# OpenAT_Switch_Latch.net
KiCad netlist of a schematic drawn in EAGLE
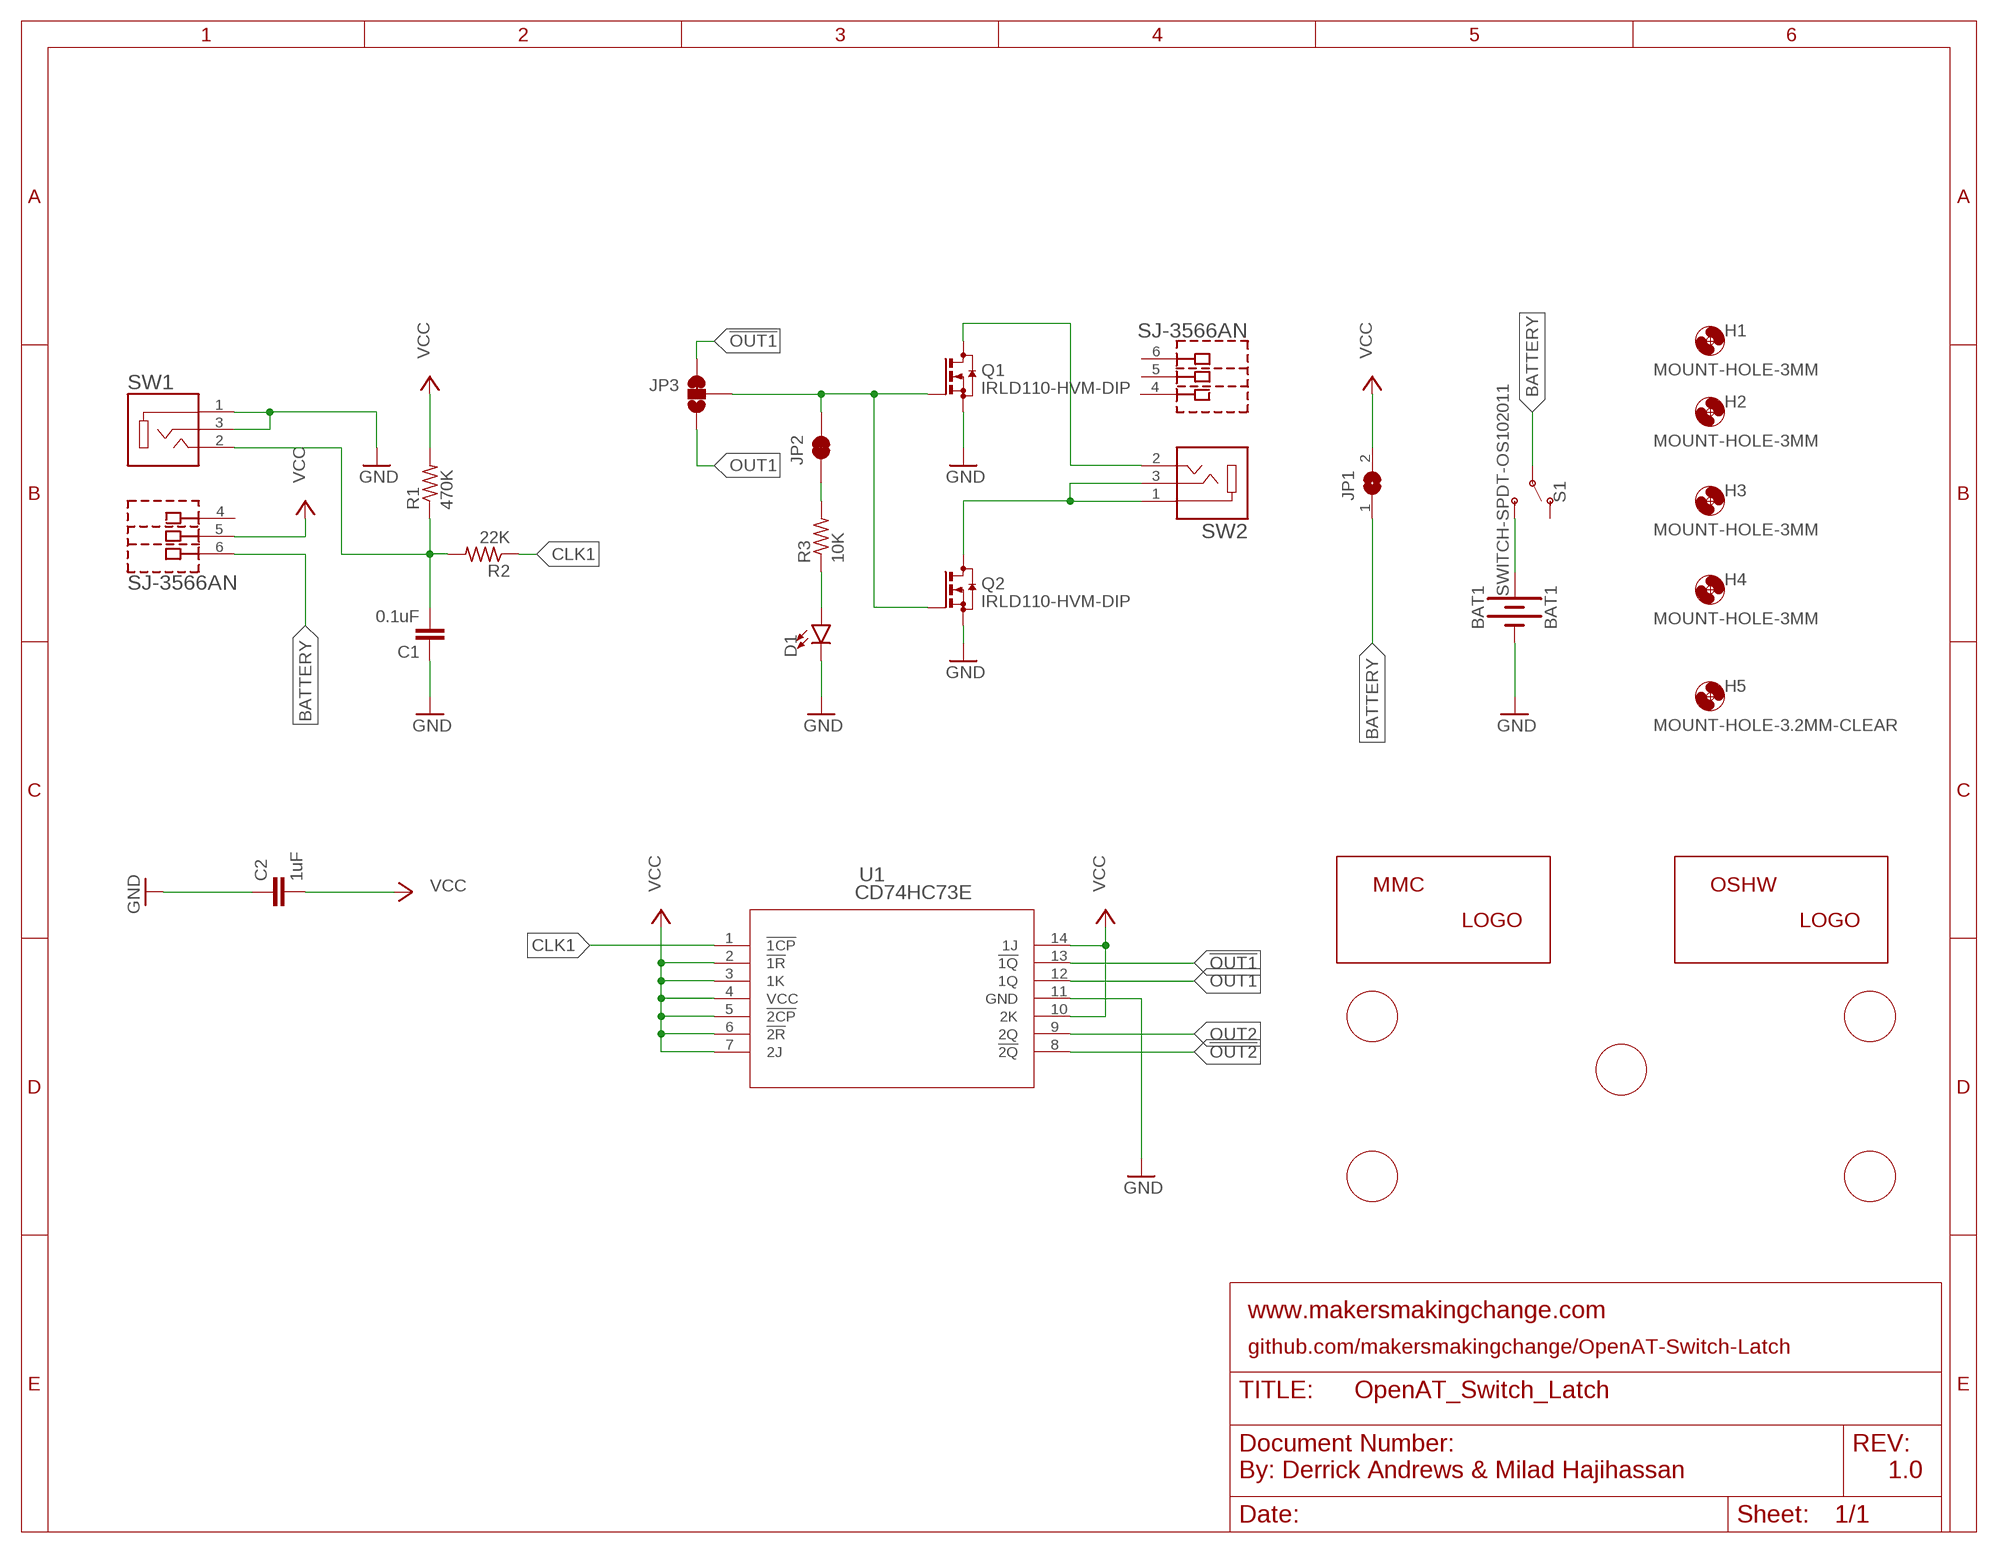
[diagram p0: schematic, sheet 1]

(export (version "E")
  (design (tool "Eeschema 10.0.6"))
  (components
    (comp (ref "BAT1")
      (value "BAT1")
      (footprint "eagle-import:BATTCOM_20MM_PTH")
      (libsource (lib "eagle-import") (part "BATTERY-20MM_PTH"))
    )
    (comp (ref "C1")
      (value "0.1uF")
      (footprint "eagle-import:CAP-050-030X075")
      (libsource (lib "eagle-import") (part "CAPACITOR-050-030-075"))
    )
    (comp (ref "C2")
      (value "1uF")
      (footprint "eagle-import:CAP-050-030X075")
      (libsource (lib "eagle-import") (part "CAPACITOR-050-030-075"))
    )
    (comp (ref "D1")
      (value "LED_5MM-5MM-GREEN")
      (footprint "eagle-import:LED_5MM_GREEN")
      (libsource (lib "eagle-import") (part "LED_5MM-5MM-GREEN"))
    )
    (comp (ref "H1")
      (value "MOUNT-HOLE-3MM")
      (footprint "eagle-import:HOLE-3MM")
      (libsource (lib "eagle-import") (part "MOUNT-HOLE-3MM"))
    )
    (comp (ref "H2")
      (value "MOUNT-HOLE-3MM")
      (footprint "eagle-import:HOLE-3MM")
      (libsource (lib "eagle-import") (part "MOUNT-HOLE-3MM"))
    )
    (comp (ref "H3")
      (value "MOUNT-HOLE-3MM")
      (footprint "eagle-import:HOLE-3MM")
      (libsource (lib "eagle-import") (part "MOUNT-HOLE-3MM"))
    )
    (comp (ref "H4")
      (value "MOUNT-HOLE-3MM")
      (footprint "eagle-import:HOLE-3MM")
      (libsource (lib "eagle-import") (part "MOUNT-HOLE-3MM"))
    )
    (comp (ref "H5")
      (value "MOUNT-HOLE-3.2MM-CLEAR")
      (footprint "eagle-import:HOLE-3.2MM-CLEAR")
      (libsource (lib "eagle-import") (part "MOUNT-HOLE-3.2MM-CLEAR"))
    )
    (comp (ref "JP1")
      (value "SOLDERJUMPEROPENED")
      (footprint "eagle-import:SOLDERJUMPER_OPENED_TRACE_SILK")
      (libsource (lib "eagle-import") (part "SOLDERJUMPEROPENED"))
    )
    (comp (ref "JP2")
      (value "JUMPERS-SMT_2_NC_TRACE_SILK")
      (footprint "eagle-import:JUMPERS_SMT-JUMPER_2_NC_TRACE_SILK")
      (libsource (lib "eagle-import") (part "JUMPERS-SMT_2_NC_TRACE_SILK"))
    )
    (comp (ref "JP3")
      (value "JUMPERS-SMT_3_1-NC_TRACE_SILK")
      (footprint "eagle-import:JUMPERS_SMT-JUMPER_3_1-NC_TRACE_SILK")
      (libsource (lib "eagle-import") (part "JUMPERS-SMT_3_1-NC_TRACE_SILK"))
    )
    (comp (ref "LABEL_INPUT")
      (value "MMC_LABEL-SW-INPUT")
      (footprint "eagle-import:LABEL-INPUT")
      (libsource (lib "eagle-import") (part "MMC_LABEL-SW-INPUT"))
    )
    (comp (ref "LABEL_LOGO")
      (value "MMC_LOGO-SM")
      (footprint "eagle-import:MMC_SMALL_LOGO")
      (libsource (lib "eagle-import") (part "MMC_LOGO-SM"))
    )
    (comp (ref "LABEL_OUTPUT")
      (value "MMC_LABEL-SW-OUTPUT")
      (footprint "eagle-import:LABEL-OUTPUT")
      (libsource (lib "eagle-import") (part "MMC_LABEL-SW-OUTPUT"))
    )
    (comp (ref "Q1")
      (value "IRLD110-HVM-DIP")
      (footprint "eagle-import:HVM-DIP")
      (libsource (lib "eagle-import") (part "IRLD110-HVM-DIP"))
    )
    (comp (ref "Q2")
      (value "IRLD110-HVM-DIP")
      (footprint "eagle-import:HVM-DIP")
      (libsource (lib "eagle-import") (part "IRLD110-HVM-DIP"))
    )
    (comp (ref "R1")
      (value "470K")
      (footprint "eagle-import:RESISTOR_0204_5")
      (libsource (lib "eagle-import") (part "RESISTOR-US-0204/5"))
    )
    (comp (ref "R2")
      (value "22K")
      (footprint "eagle-import:RESISTOR_0204_5")
      (libsource (lib "eagle-import") (part "RESISTOR-US-0204/5"))
    )
    (comp (ref "R3")
      (value "10K")
      (footprint "eagle-import:RESISTOR_0204_5")
      (libsource (lib "eagle-import") (part "RESISTOR-US-0204/5"))
    )
    (comp (ref "S1")
      (value "SWITCH-SPDT-OS102011")
      (footprint "eagle-import:SWITCH_SPDT_11MA1QS1")
      (libsource (lib "eagle-import") (part "SWITCH-SPDT-OS102011"))
    )
    (comp (ref "SW1")
      (value "SJ-3566AN")
      (footprint "eagle-import:CUI_SJ-3566AN")
      (fields (field (name "DIGI-KEY_PART_NUMBER") "CP-SJ-3566AN-ND") (field (name "MF") "CUI Devices"))
      (libsource (lib "eagle-import") (part "SJ-3566AN"))
    )
    (comp (ref "SW2")
      (value "SJ-3566AN")
      (footprint "eagle-import:CUI_SJ-3566AN")
      (fields (field (name "DIGI-KEY_PART_NUMBER") "CP-SJ-3566AN-ND") (field (name "MF") "CUI Devices"))
      (libsource (lib "eagle-import") (part "SJ-3566AN"))
    )
    (comp (ref "U$1")
      (value "OSHW_LOGO-XSM")
      (footprint "eagle-import:OSHW_X-SMALL_LOGO")
      (libsource (lib "eagle-import") (part "OSHW_LOGO-XSM"))
    )
    (comp (ref "U$2")
      (value "MMC_LABEL-OPENAT")
      (footprint "eagle-import:LABEL-OPENAT")
      (libsource (lib "eagle-import") (part "MMC_LABEL-OPENAT"))
    )
    (comp (ref "U$3")
      (value "MMC_LABEL-SWITCH-LATCH")
      (footprint "eagle-import:LABEL-SWITCH-LATCH")
      (libsource (lib "eagle-import") (part "MMC_LABEL-SWITCH-LATCH"))
    )
    (comp (ref "U$4")
      (value "MMC_LABEL-V1.0")
      (footprint "eagle-import:LABEL-V1.0")
      (libsource (lib "eagle-import") (part "MMC_LABEL-V1.0"))
    )
    (comp (ref "U1")
      (value "CD74HC73E")
      (footprint "eagle-import:14-DIP")
      (fields (field (name "COPYRIGHT") "Copyright (C) 2022 Ultra Librarian. All rights reserved."))
      (libsource (lib "eagle-import") (part "CD74HC73E"))
    )
  )
  (nets
    (net (code "1") (name "/~{OUT1}") (class "Default")
      (node (ref "JP3") (pin "1") (pinfunction "1_1") (pintype "passive"))
      (node (ref "U1") (pin "13") (pinfunction "~{1Q}_13") (pintype "output"))
    )
    (net (code "2") (name "/~{OUT2}") (class "Default")
      (node (ref "U1") (pin "8") (pinfunction "~{2Q}_8") (pintype "output"))
    )
    (net (code "3") (name "BATTERY") (class "Default")
      (node (ref "JP1") (pin "1") (pinfunction "1_1") (pintype "passive"))
      (node (ref "S1") (pin "2") (pinfunction "P_2") (pintype "passive"))
      (node (ref "SW1") (pin "6") (pinfunction "6_6") (pintype "passive"))
    )
    (net (code "4") (name "CLK1") (class "Default")
      (node (ref "R2") (pin "1") (pinfunction "1_1") (pintype "passive"))
      (node (ref "U1") (pin "1") (pinfunction "~{1CP}_1") (pintype "input"))
    )
    (net (code "5") (name "GND") (class "Default")
      (node (ref "BAT1") (pin "-") (pinfunction "-_-") (pintype "power_in"))
      (node (ref "C1") (pin "1") (pinfunction "1_1") (pintype "passive"))
      (node (ref "C2") (pin "1") (pinfunction "1_1") (pintype "passive"))
      (node (ref "D1") (pin "K") (pinfunction "C_K") (pintype "passive"))
      (node (ref "Q1") (pin "2") (pinfunction "S_2") (pintype "passive"))
      (node (ref "Q2") (pin "2") (pinfunction "S_2") (pintype "passive"))
      (node (ref "SW1") (pin "1") (pinfunction "1_1") (pintype "passive"))
      (node (ref "SW1") (pin "3") (pinfunction "3_3") (pintype "passive"))
      (node (ref "U1") (pin "11") (pinfunction "GND_11") (pintype "power_in"))
    )
    (net (code "6") (name "Net-(C1-Pad2)") (class "Default")
      (node (ref "C1") (pin "2") (pinfunction "2_2") (pintype "passive"))
      (node (ref "R1") (pin "1") (pinfunction "1_1") (pintype "passive"))
      (node (ref "R2") (pin "2") (pinfunction "2_2") (pintype "passive"))
      (node (ref "SW1") (pin "2") (pinfunction "2_2") (pintype "passive"))
    )
    (net (code "7") (name "Net-(D1-PadA)") (class "Default")
      (node (ref "D1") (pin "A") (pinfunction "A_A") (pintype "passive"))
      (node (ref "R3") (pin "1") (pinfunction "1_1") (pintype "passive"))
    )
    (net (code "8") (name "Net-(JP2-Pad1)") (class "Default")
      (node (ref "JP2") (pin "1") (pinfunction "1_1") (pintype "passive"))
      (node (ref "R3") (pin "2") (pinfunction "2_2") (pintype "passive"))
    )
    (net (code "9") (name "Net-(Q1-D)") (class "Default")
      (node (ref "Q1") (pin "3") (pinfunction "D_3") (pintype "passive"))
      (node (ref "SW2") (pin "2") (pinfunction "2_2") (pintype "passive"))
    )
    (net (code "10") (name "Net-(Q1-G)") (class "Default")
      (node (ref "JP2") (pin "2") (pinfunction "2_2") (pintype "passive"))
      (node (ref "JP3") (pin "2") (pinfunction "2_2") (pintype "passive"))
      (node (ref "Q1") (pin "1") (pinfunction "G_1") (pintype "passive"))
      (node (ref "Q2") (pin "1") (pinfunction "G_1") (pintype "passive"))
    )
    (net (code "11") (name "Net-(Q2-D)") (class "Default")
      (node (ref "Q2") (pin "3") (pinfunction "D_3") (pintype "passive"))
      (node (ref "SW2") (pin "1") (pinfunction "1_1") (pintype "passive"))
      (node (ref "SW2") (pin "3") (pinfunction "3_3") (pintype "passive"))
    )
    (net (code "12") (name "Net-(S1-S)") (class "Default")
      (node (ref "BAT1") (pin "+") (pinfunction "+_+") (pintype "power_in"))
      (node (ref "S1") (pin "3") (pinfunction "S_3") (pintype "passive"))
    )
    (net (code "13") (name "OUT1") (class "Default")
      (node (ref "JP3") (pin "3") (pinfunction "3_3") (pintype "passive"))
      (node (ref "U1") (pin "12") (pinfunction "1Q_12") (pintype "output"))
    )
    (net (code "14") (name "OUT2") (class "Default")
      (node (ref "U1") (pin "9") (pinfunction "2Q_9") (pintype "output"))
    )
    (net (code "15") (name "VCC") (class "Default")
      (node (ref "C2") (pin "2") (pinfunction "2_2") (pintype "passive"))
      (node (ref "JP1") (pin "2") (pinfunction "2_2") (pintype "passive"))
      (node (ref "R1") (pin "2") (pinfunction "2_2") (pintype "passive"))
      (node (ref "SW1") (pin "5") (pinfunction "5_5") (pintype "passive"))
      (node (ref "U1") (pin "10") (pinfunction "2K_10") (pintype "input"))
      (node (ref "U1") (pin "14") (pinfunction "1J_14") (pintype "input"))
      (node (ref "U1") (pin "2") (pinfunction "~{1R}_2") (pintype "input"))
      (node (ref "U1") (pin "3") (pinfunction "1K_3") (pintype "input"))
      (node (ref "U1") (pin "4") (pinfunction "VCC_4") (pintype "power_in"))
      (node (ref "U1") (pin "5") (pinfunction "~{2CP}_5") (pintype "input"))
      (node (ref "U1") (pin "6") (pinfunction "~{2R}_6") (pintype "input"))
      (node (ref "U1") (pin "7") (pinfunction "2J_7") (pintype "input"))
    )
    (net (code "16") (name "unconnected-(S1-O-Pad1)") (class "Default")
      (node (ref "S1") (pin "1") (pinfunction "O_1") (pintype "passive"))
    )
    (net (code "17") (name "unconnected-(SW1-Pad4)") (class "Default")
      (node (ref "SW1") (pin "4") (pinfunction "4_4") (pintype "passive"))
    )
    (net (code "18") (name "unconnected-(SW2-Pad4)") (class "Default")
      (node (ref "SW2") (pin "4") (pinfunction "4_4") (pintype "passive"))
    )
    (net (code "19") (name "unconnected-(SW2-Pad5)") (class "Default")
      (node (ref "SW2") (pin "5") (pinfunction "5_5") (pintype "passive"))
    )
    (net (code "20") (name "unconnected-(SW2-Pad6)") (class "Default")
      (node (ref "SW2") (pin "6") (pinfunction "6_6") (pintype "passive"))
    )
  )
)
